# sigsub.net
KiCad netlist of a schematic drawn in Altium Designer
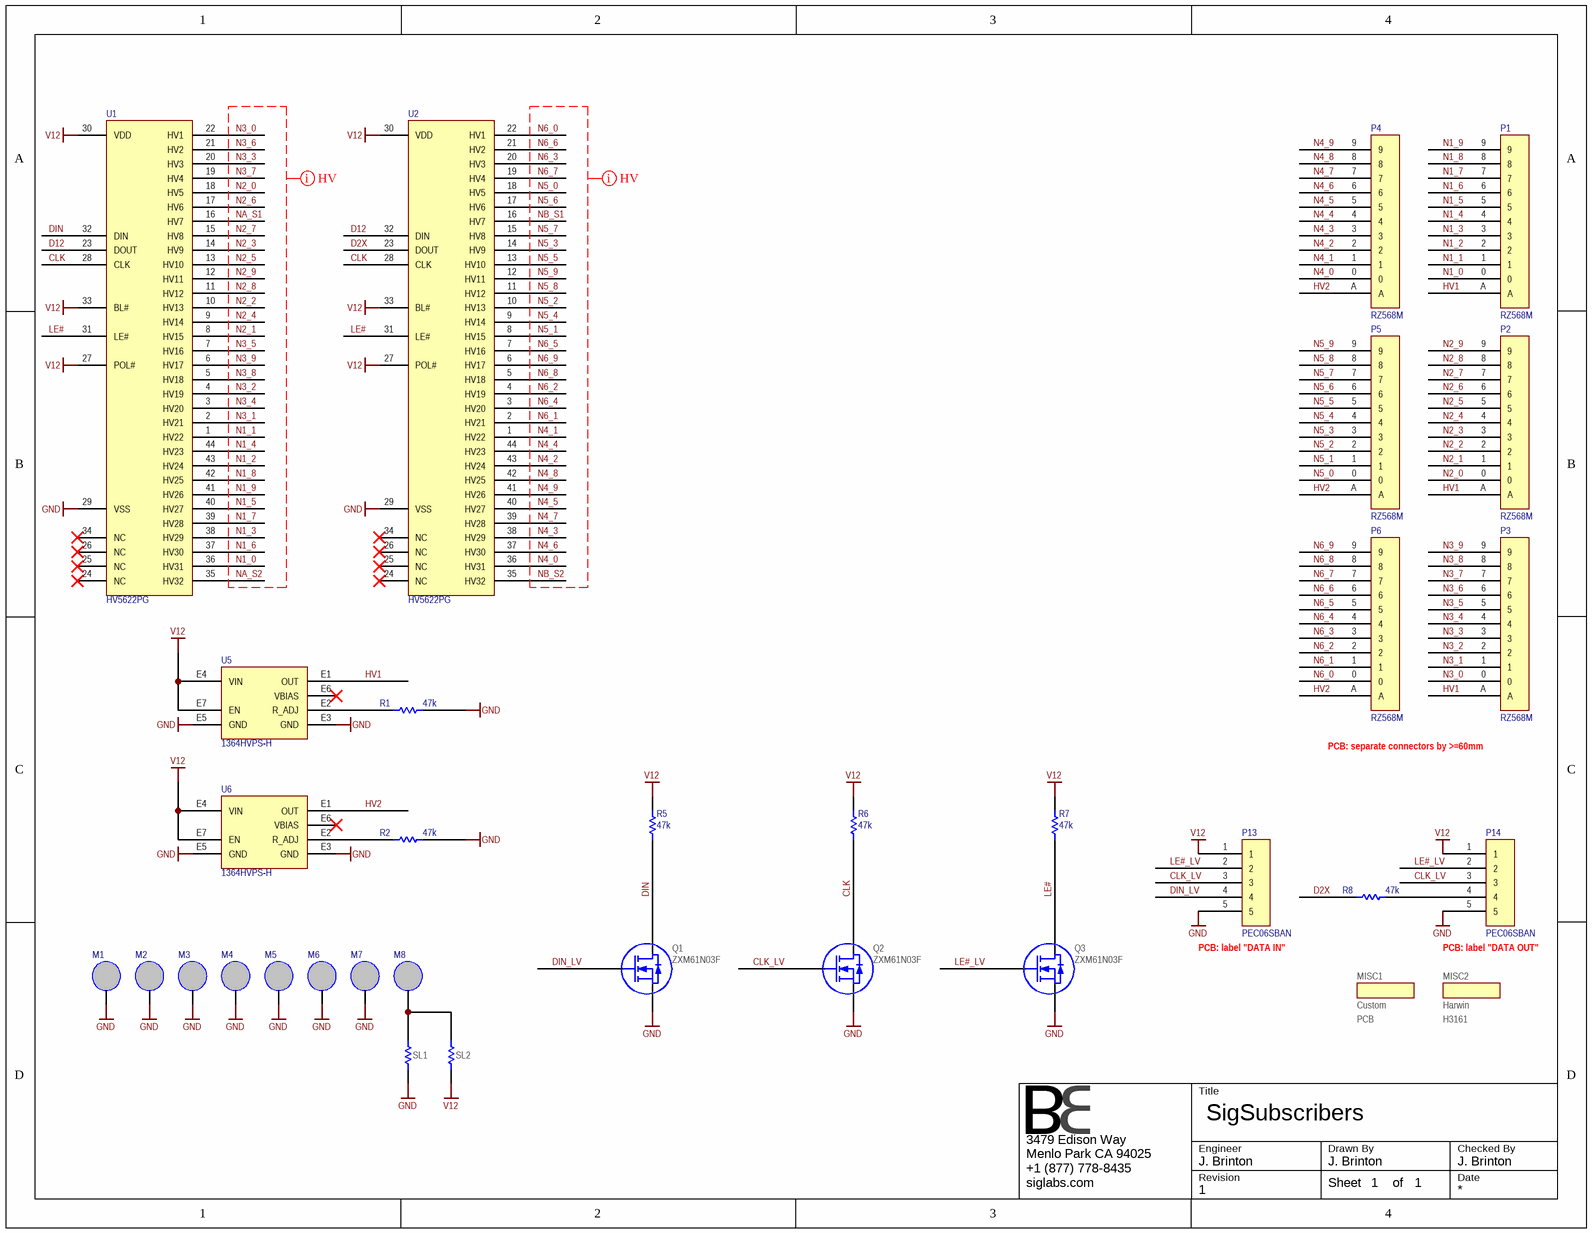
[diagram p0: sigsub.SchDoc]

(export (version "E")
  (design (tool "Eeschema 10.0.6"))
  (components
    (comp (ref "M1") (value "MOUNT") (footprint "MOUNT1-4_20") (libsource (lib "generic") (part "MOUNT")))
    (comp (ref "M2") (value "MOUNT") (footprint "MOUNT1-4_20") (libsource (lib "generic") (part "MOUNT")))
    (comp (ref "M3") (value "MOUNT") (footprint "MOUNT1-4_20") (libsource (lib "generic") (part "MOUNT")))
    (comp (ref "M4") (value "MOUNT") (footprint "MOUNT1-4_20") (libsource (lib "generic") (part "MOUNT")))
    (comp (ref "M5") (value "MOUNT") (footprint "MOUNT1-4_20") (libsource (lib "generic") (part "MOUNT")))
    (comp (ref "M6") (value "MOUNT") (footprint "MOUNT1-4_20") (libsource (lib "generic") (part "MOUNT")))
    (comp (ref "M7") (value "MOUNT") (footprint "MOUNT1-4_20") (libsource (lib "generic") (part "MOUNT")))
    (comp (ref "M8") (value "MOUNT") (footprint "MOUNT1-4_20") (libsource (lib "generic") (part "MOUNT")))
    (comp (ref "MISC1")
      (value "PCB")
      (fields (field (name "MANUFACTURER") "Custom"))
      (libsource (lib "harwin") (part "M50-1900005"))
    )
    (comp (ref "MISC2")
      (value "H3161")
      (description "Pin Receptacle")
      (fields (field (name "MANUFACTURER") "Harwin"))
      (libsource (lib "harwin") (part "M50-1900005"))
    )
    (comp (ref "P1")
      (value "RZ568M")
      (footprint "RZ568M")
      (description "Nixie Tube Socket")
      (fields (field (name "MANUFACTURER") "Glow Tube Research"))
      (libsource (lib "sigsub") (part "RZ568M"))
    )
    (comp (ref "P2")
      (value "RZ568M")
      (footprint "RZ568M")
      (description "Nixie Tube Socket")
      (fields (field (name "MANUFACTURER") "Glow Tube Research"))
      (libsource (lib "sigsub") (part "RZ568M"))
    )
    (comp (ref "P3")
      (value "RZ568M")
      (footprint "RZ568M")
      (description "Nixie Tube Socket")
      (fields (field (name "MANUFACTURER") "Glow Tube Research"))
      (libsource (lib "sigsub") (part "RZ568M"))
    )
    (comp (ref "P4")
      (value "RZ568M")
      (footprint "RZ568M")
      (description "Nixie Tube Socket")
      (fields (field (name "MANUFACTURER") "Glow Tube Research"))
      (libsource (lib "sigsub") (part "RZ568M"))
    )
    (comp (ref "P5")
      (value "RZ568M")
      (footprint "RZ568M")
      (description "Nixie Tube Socket")
      (fields (field (name "MANUFACTURER") "Glow Tube Research"))
      (libsource (lib "sigsub") (part "RZ568M"))
    )
    (comp (ref "P6")
      (value "RZ568M")
      (footprint "RZ568M")
      (description "Nixie Tube Socket")
      (fields (field (name "MANUFACTURER") "Glow Tube Research"))
      (libsource (lib "sigsub") (part "RZ568M"))
    )
    (comp (ref "P13")
      (value "PEC06SBAN")
      (footprint "HDR1X5")
      (description "Header, 5-Pin, Right Angle, 0.1\" pitch")
      (fields (field (name "MANUFACTURER") "Sullins"))
      (libsource (lib "sigsub") (part "PEC06SBAN"))
    )
    (comp (ref "P14")
      (value "PEC06SBAN")
      (footprint "HDR1X5")
      (description "Header, 5-Pin, Right Angle, 0.1\" pitch")
      (fields (field (name "MANUFACTURER") "Sullins"))
      (libsource (lib "sigsub") (part "PEC06SBAN"))
    )
    (comp (ref "Q1")
      (value "ZXM61N03F")
      (footprint "SOT23")
      (description "N-Channel Enhancement Mode MOSFET transistor")
      (fields (field (name "MANUFACTURER") "Zetex"))
      (libsource (lib "nxp") (part "BSH103"))
    )
    (comp (ref "Q2")
      (value "ZXM61N03F")
      (footprint "SOT23")
      (description "N-Channel Enhancement Mode MOSFET transistor")
      (fields (field (name "MANUFACTURER") "Zetex"))
      (libsource (lib "nxp") (part "BSH103"))
    )
    (comp (ref "Q3")
      (value "ZXM61N03F")
      (footprint "SOT23")
      (description "N-Channel Enhancement Mode MOSFET transistor")
      (fields (field (name "MANUFACTURER") "Zetex"))
      (libsource (lib "nxp") (part "BSH103"))
    )
    (comp (ref "R1")
      (value "47k")
      (footprint "0805")
      (description "Thick Film Resistor 47k +/-1% 0805")
      (fields (field (name "MANUFACTURER") "Panasonic") (field (name "Comment") "ERJ-6ENF4702V"))
      (libsource (lib "generic") (part "RES"))
    )
    (comp (ref "R2")
      (value "47k")
      (footprint "0805")
      (description "Thick Film Resistor 47k +/-1% 0805")
      (fields (field (name "MANUFACTURER") "Panasonic") (field (name "Comment") "ERJ-6ENF4702V"))
      (libsource (lib "generic") (part "RES"))
    )
    (comp (ref "R5")
      (value "47k")
      (footprint "0805")
      (description "Thick Film Resistor 47k +/-1% 0805")
      (fields (field (name "MANUFACTURER") "Panasonic") (field (name "Comment") "ERJ-6ENF4702V"))
      (libsource (lib "generic") (part "RES"))
    )
    (comp (ref "R6")
      (value "47k")
      (footprint "0805")
      (description "Thick Film Resistor 47k +/-1% 0805")
      (fields (field (name "MANUFACTURER") "Panasonic") (field (name "Comment") "ERJ-6ENF4702V"))
      (libsource (lib "generic") (part "RES"))
    )
    (comp (ref "R7")
      (value "47k")
      (footprint "0805")
      (description "Thick Film Resistor 47k +/-1% 0805")
      (fields (field (name "MANUFACTURER") "Panasonic") (field (name "Comment") "ERJ-6ENF4702V"))
      (libsource (lib "generic") (part "RES"))
    )
    (comp (ref "R8")
      (value "47k")
      (footprint "0805")
      (description "Thick Film Resistor 47k +/-1% 0805")
      (fields (field (name "MANUFACTURER") "Panasonic") (field (name "Comment") "ERJ-6ENF4702V"))
      (libsource (lib "generic") (part "RES"))
    )
    (comp (ref "SL1")
      (value "SOLDER_LINK")
      (footprint "SOLDERLINK0603X26N")
      (description "Solder Link")
      (libsource (lib "generic") (part "RES"))
    )
    (comp (ref "SL2")
      (value "SOLDER_LINK")
      (footprint "SOLDERLINK0603X26N")
      (description "Solder Link")
      (libsource (lib "generic") (part "RES"))
    )
    (comp (ref "U1")
      (value "HV5622PG")
      (footprint "QFP44P80_1390X1390X235L88X37N")
      (description "32-Channel Serial to Parallel Converter")
      (fields (field (name "MANUFACTURER") "Microchip"))
      (libsource (lib "sigsub") (part "HV5622PG"))
    )
    (comp (ref "U2")
      (value "HV5622PG")
      (footprint "QFP44P80_1390X1390X235L88X37N")
      (description "32-Channel Serial to Parallel Converter")
      (fields (field (name "MANUFACTURER") "Microchip"))
      (libsource (lib "sigsub") (part "HV5622PG"))
    )
    (comp (ref "U5")
      (value "1364HVPS-H")
      (footprint "1364HVPS-H")
      (description "High Voltage Power Supply")
      (fields (field (name "MANUFACTURER") "Taylor Electronics"))
      (libsource (lib "sigsub") (part "1364HVPS-H"))
    )
    (comp (ref "U6")
      (value "1364HVPS-H")
      (footprint "1364HVPS-H")
      (description "High Voltage Power Supply")
      (fields (field (name "MANUFACTURER") "Taylor Electronics"))
      (libsource (lib "sigsub") (part "1364HVPS-H"))
    )
  )
  (nets
    (net (code "1") (name "/CLK") (class "Default")
      (node (ref "Q2") (pin "3") (pinfunction "D_3") (pintype "passive"))
      (node (ref "R6") (pin "1") (pinfunction "1_1") (pintype "passive"))
      (node (ref "U1") (pin "28") (pinfunction "CLK_28") (pintype "passive"))
      (node (ref "U2") (pin "28") (pinfunction "CLK_28") (pintype "passive"))
    )
    (net (code "2") (name "/CLK_LV") (class "Default")
      (node (ref "P13") (pin "3") (pinfunction "3_3") (pintype "passive"))
      (node (ref "P14") (pin "3") (pinfunction "3_3") (pintype "passive"))
      (node (ref "Q2") (pin "1") (pinfunction "G_1") (pintype "passive"))
    )
    (net (code "3") (name "/D2X") (class "Default")
      (node (ref "R8") (pin "1") (pinfunction "1_1") (pintype "passive"))
      (node (ref "U2") (pin "23") (pinfunction "DOUT_23") (pintype "passive"))
    )
    (net (code "4") (name "/D12") (class "Default")
      (node (ref "U1") (pin "23") (pinfunction "DOUT_23") (pintype "passive"))
      (node (ref "U2") (pin "32") (pinfunction "DIN_32") (pintype "passive"))
    )
    (net (code "5") (name "/DIN") (class "Default")
      (node (ref "Q1") (pin "3") (pinfunction "D_3") (pintype "passive"))
      (node (ref "R5") (pin "1") (pinfunction "1_1") (pintype "passive"))
      (node (ref "U1") (pin "32") (pinfunction "DIN_32") (pintype "passive"))
    )
    (net (code "6") (name "/DIN_LV") (class "Default")
      (node (ref "P13") (pin "4") (pinfunction "4_4") (pintype "passive"))
      (node (ref "Q1") (pin "1") (pinfunction "G_1") (pintype "passive"))
    )
    (net (code "7") (name "/HV1") (class "Default")
      (node (ref "P1") (pin "A") (pinfunction "A_A") (pintype "passive"))
      (node (ref "P2") (pin "A") (pinfunction "A_A") (pintype "passive"))
      (node (ref "P3") (pin "A") (pinfunction "A_A") (pintype "passive"))
      (node (ref "U5") (pin "E1") (pinfunction "OUT_E1") (pintype "passive"))
    )
    (net (code "8") (name "/HV2") (class "Default")
      (node (ref "P4") (pin "A") (pinfunction "A_A") (pintype "passive"))
      (node (ref "P5") (pin "A") (pinfunction "A_A") (pintype "passive"))
      (node (ref "P6") (pin "A") (pinfunction "A_A") (pintype "passive"))
      (node (ref "U6") (pin "E1") (pinfunction "OUT_E1") (pintype "passive"))
    )
    (net (code "9") (name "/LE#") (class "Default")
      (node (ref "Q3") (pin "3") (pinfunction "D_3") (pintype "passive"))
      (node (ref "R7") (pin "1") (pinfunction "1_1") (pintype "passive"))
      (node (ref "U1") (pin "31") (pinfunction "LE#_31") (pintype "passive"))
      (node (ref "U2") (pin "31") (pinfunction "LE#_31") (pintype "passive"))
    )
    (net (code "10") (name "/LE#_LV") (class "Default")
      (node (ref "P13") (pin "2") (pinfunction "2_2") (pintype "passive"))
      (node (ref "P14") (pin "2") (pinfunction "2_2") (pintype "passive"))
      (node (ref "Q3") (pin "1") (pinfunction "G_1") (pintype "passive"))
    )
    (net (code "11") (name "/N1_0") (class "Default")
      (node (ref "P1") (pin "0") (pinfunction "0_0") (pintype "passive"))
      (node (ref "U1") (pin "36") (pinfunction "HV31_36") (pintype "passive"))
    )
    (net (code "12") (name "/N1_1") (class "Default")
      (node (ref "P1") (pin "1") (pinfunction "1_1") (pintype "passive"))
      (node (ref "U1") (pin "1") (pinfunction "HV22_1") (pintype "passive"))
    )
    (net (code "13") (name "/N1_2") (class "Default")
      (node (ref "P1") (pin "2") (pinfunction "2_2") (pintype "passive"))
      (node (ref "U1") (pin "43") (pinfunction "HV24_43") (pintype "passive"))
    )
    (net (code "14") (name "/N1_3") (class "Default")
      (node (ref "P1") (pin "3") (pinfunction "3_3") (pintype "passive"))
      (node (ref "U1") (pin "38") (pinfunction "HV29_38") (pintype "passive"))
    )
    (net (code "15") (name "/N1_4") (class "Default")
      (node (ref "P1") (pin "4") (pinfunction "4_4") (pintype "passive"))
      (node (ref "U1") (pin "44") (pinfunction "HV23_44") (pintype "passive"))
    )
    (net (code "16") (name "/N1_5") (class "Default")
      (node (ref "P1") (pin "5") (pinfunction "5_5") (pintype "passive"))
      (node (ref "U1") (pin "40") (pinfunction "HV27_40") (pintype "passive"))
    )
    (net (code "17") (name "/N1_6") (class "Default")
      (node (ref "P1") (pin "6") (pinfunction "6_6") (pintype "passive"))
      (node (ref "U1") (pin "37") (pinfunction "HV30_37") (pintype "passive"))
    )
    (net (code "18") (name "/N1_7") (class "Default")
      (node (ref "P1") (pin "7") (pinfunction "7_7") (pintype "passive"))
      (node (ref "U1") (pin "39") (pinfunction "HV28_39") (pintype "passive"))
    )
    (net (code "19") (name "/N1_8") (class "Default")
      (node (ref "P1") (pin "8") (pinfunction "8_8") (pintype "passive"))
      (node (ref "U1") (pin "42") (pinfunction "HV25_42") (pintype "passive"))
    )
    (net (code "20") (name "/N1_9") (class "Default")
      (node (ref "P1") (pin "9") (pinfunction "9_9") (pintype "passive"))
      (node (ref "U1") (pin "41") (pinfunction "HV26_41") (pintype "passive"))
    )
    (net (code "21") (name "/N2_0") (class "Default")
      (node (ref "P2") (pin "0") (pinfunction "0_0") (pintype "passive"))
      (node (ref "U1") (pin "18") (pinfunction "HV5_18") (pintype "passive"))
    )
    (net (code "22") (name "/N2_1") (class "Default")
      (node (ref "P2") (pin "1") (pinfunction "1_1") (pintype "passive"))
      (node (ref "U1") (pin "8") (pinfunction "HV15_8") (pintype "passive"))
    )
    (net (code "23") (name "/N2_2") (class "Default")
      (node (ref "P2") (pin "2") (pinfunction "2_2") (pintype "passive"))
      (node (ref "U1") (pin "10") (pinfunction "HV13_10") (pintype "passive"))
    )
    (net (code "24") (name "/N2_3") (class "Default")
      (node (ref "P2") (pin "3") (pinfunction "3_3") (pintype "passive"))
      (node (ref "U1") (pin "14") (pinfunction "HV9_14") (pintype "passive"))
    )
    (net (code "25") (name "/N2_4") (class "Default")
      (node (ref "P2") (pin "4") (pinfunction "4_4") (pintype "passive"))
      (node (ref "U1") (pin "9") (pinfunction "HV14_9") (pintype "passive"))
    )
    (net (code "26") (name "/N2_5") (class "Default")
      (node (ref "P2") (pin "5") (pinfunction "5_5") (pintype "passive"))
      (node (ref "U1") (pin "13") (pinfunction "HV10_13") (pintype "passive"))
    )
    (net (code "27") (name "/N2_6") (class "Default")
      (node (ref "P2") (pin "6") (pinfunction "6_6") (pintype "passive"))
      (node (ref "U1") (pin "17") (pinfunction "HV6_17") (pintype "passive"))
    )
    (net (code "28") (name "/N2_7") (class "Default")
      (node (ref "P2") (pin "7") (pinfunction "7_7") (pintype "passive"))
      (node (ref "U1") (pin "15") (pinfunction "HV8_15") (pintype "passive"))
    )
    (net (code "29") (name "/N2_8") (class "Default")
      (node (ref "P2") (pin "8") (pinfunction "8_8") (pintype "passive"))
      (node (ref "U1") (pin "11") (pinfunction "HV12_11") (pintype "passive"))
    )
    (net (code "30") (name "/N2_9") (class "Default")
      (node (ref "P2") (pin "9") (pinfunction "9_9") (pintype "passive"))
      (node (ref "U1") (pin "12") (pinfunction "HV11_12") (pintype "passive"))
    )
    (net (code "31") (name "/N3_0") (class "Default")
      (node (ref "P3") (pin "0") (pinfunction "0_0") (pintype "passive"))
      (node (ref "U1") (pin "22") (pinfunction "HV1_22") (pintype "passive"))
    )
    (net (code "32") (name "/N3_1") (class "Default")
      (node (ref "P3") (pin "1") (pinfunction "1_1") (pintype "passive"))
      (node (ref "U1") (pin "2") (pinfunction "HV21_2") (pintype "passive"))
    )
    (net (code "33") (name "/N3_2") (class "Default")
      (node (ref "P3") (pin "2") (pinfunction "2_2") (pintype "passive"))
      (node (ref "U1") (pin "4") (pinfunction "HV19_4") (pintype "passive"))
    )
    (net (code "34") (name "/N3_3") (class "Default")
      (node (ref "P3") (pin "3") (pinfunction "3_3") (pintype "passive"))
      (node (ref "U1") (pin "20") (pinfunction "HV3_20") (pintype "passive"))
    )
    (net (code "35") (name "/N3_4") (class "Default")
      (node (ref "P3") (pin "4") (pinfunction "4_4") (pintype "passive"))
      (node (ref "U1") (pin "3") (pinfunction "HV20_3") (pintype "passive"))
    )
    (net (code "36") (name "/N3_5") (class "Default")
      (node (ref "P3") (pin "5") (pinfunction "5_5") (pintype "passive"))
      (node (ref "U1") (pin "7") (pinfunction "HV16_7") (pintype "passive"))
    )
    (net (code "37") (name "/N3_6") (class "Default")
      (node (ref "P3") (pin "6") (pinfunction "6_6") (pintype "passive"))
      (node (ref "U1") (pin "21") (pinfunction "HV2_21") (pintype "passive"))
    )
    (net (code "38") (name "/N3_7") (class "Default")
      (node (ref "P3") (pin "7") (pinfunction "7_7") (pintype "passive"))
      (node (ref "U1") (pin "19") (pinfunction "HV4_19") (pintype "passive"))
    )
    (net (code "39") (name "/N3_8") (class "Default")
      (node (ref "P3") (pin "8") (pinfunction "8_8") (pintype "passive"))
      (node (ref "U1") (pin "5") (pinfunction "HV18_5") (pintype "passive"))
    )
    (net (code "40") (name "/N3_9") (class "Default")
      (node (ref "P3") (pin "9") (pinfunction "9_9") (pintype "passive"))
      (node (ref "U1") (pin "6") (pinfunction "HV17_6") (pintype "passive"))
    )
    (net (code "41") (name "/N4_0") (class "Default")
      (node (ref "P4") (pin "0") (pinfunction "0_0") (pintype "passive"))
      (node (ref "U2") (pin "36") (pinfunction "HV31_36") (pintype "passive"))
    )
    (net (code "42") (name "/N4_1") (class "Default")
      (node (ref "P4") (pin "1") (pinfunction "1_1") (pintype "passive"))
      (node (ref "U2") (pin "1") (pinfunction "HV22_1") (pintype "passive"))
    )
    (net (code "43") (name "/N4_2") (class "Default")
      (node (ref "P4") (pin "2") (pinfunction "2_2") (pintype "passive"))
      (node (ref "U2") (pin "43") (pinfunction "HV24_43") (pintype "passive"))
    )
    (net (code "44") (name "/N4_3") (class "Default")
      (node (ref "P4") (pin "3") (pinfunction "3_3") (pintype "passive"))
      (node (ref "U2") (pin "38") (pinfunction "HV29_38") (pintype "passive"))
    )
    (net (code "45") (name "/N4_4") (class "Default")
      (node (ref "P4") (pin "4") (pinfunction "4_4") (pintype "passive"))
      (node (ref "U2") (pin "44") (pinfunction "HV23_44") (pintype "passive"))
    )
    (net (code "46") (name "/N4_5") (class "Default")
      (node (ref "P4") (pin "5") (pinfunction "5_5") (pintype "passive"))
      (node (ref "U2") (pin "40") (pinfunction "HV27_40") (pintype "passive"))
    )
    (net (code "47") (name "/N4_6") (class "Default")
      (node (ref "P4") (pin "6") (pinfunction "6_6") (pintype "passive"))
      (node (ref "U2") (pin "37") (pinfunction "HV30_37") (pintype "passive"))
    )
    (net (code "48") (name "/N4_7") (class "Default")
      (node (ref "P4") (pin "7") (pinfunction "7_7") (pintype "passive"))
      (node (ref "U2") (pin "39") (pinfunction "HV28_39") (pintype "passive"))
    )
    (net (code "49") (name "/N4_8") (class "Default")
      (node (ref "P4") (pin "8") (pinfunction "8_8") (pintype "passive"))
      (node (ref "U2") (pin "42") (pinfunction "HV25_42") (pintype "passive"))
    )
    (net (code "50") (name "/N4_9") (class "Default")
      (node (ref "P4") (pin "9") (pinfunction "9_9") (pintype "passive"))
      (node (ref "U2") (pin "41") (pinfunction "HV26_41") (pintype "passive"))
    )
    (net (code "51") (name "/N5_0") (class "Default")
      (node (ref "P5") (pin "0") (pinfunction "0_0") (pintype "passive"))
      (node (ref "U2") (pin "18") (pinfunction "HV5_18") (pintype "passive"))
    )
    (net (code "52") (name "/N5_1") (class "Default")
      (node (ref "P5") (pin "1") (pinfunction "1_1") (pintype "passive"))
      (node (ref "U2") (pin "8") (pinfunction "HV15_8") (pintype "passive"))
    )
    (net (code "53") (name "/N5_2") (class "Default")
      (node (ref "P5") (pin "2") (pinfunction "2_2") (pintype "passive"))
      (node (ref "U2") (pin "10") (pinfunction "HV13_10") (pintype "passive"))
    )
    (net (code "54") (name "/N5_3") (class "Default")
      (node (ref "P5") (pin "3") (pinfunction "3_3") (pintype "passive"))
      (node (ref "U2") (pin "14") (pinfunction "HV9_14") (pintype "passive"))
    )
    (net (code "55") (name "/N5_4") (class "Default")
      (node (ref "P5") (pin "4") (pinfunction "4_4") (pintype "passive"))
      (node (ref "U2") (pin "9") (pinfunction "HV14_9") (pintype "passive"))
    )
    (net (code "56") (name "/N5_5") (class "Default")
      (node (ref "P5") (pin "5") (pinfunction "5_5") (pintype "passive"))
      (node (ref "U2") (pin "13") (pinfunction "HV10_13") (pintype "passive"))
    )
    (net (code "57") (name "/N5_6") (class "Default")
      (node (ref "P5") (pin "6") (pinfunction "6_6") (pintype "passive"))
      (node (ref "U2") (pin "17") (pinfunction "HV6_17") (pintype "passive"))
    )
    (net (code "58") (name "/N5_7") (class "Default")
      (node (ref "P5") (pin "7") (pinfunction "7_7") (pintype "passive"))
      (node (ref "U2") (pin "15") (pinfunction "HV8_15") (pintype "passive"))
    )
    (net (code "59") (name "/N5_8") (class "Default")
      (node (ref "P5") (pin "8") (pinfunction "8_8") (pintype "passive"))
      (node (ref "U2") (pin "11") (pinfunction "HV12_11") (pintype "passive"))
    )
    (net (code "60") (name "/N5_9") (class "Default")
      (node (ref "P5") (pin "9") (pinfunction "9_9") (pintype "passive"))
      (node (ref "U2") (pin "12") (pinfunction "HV11_12") (pintype "passive"))
    )
    (net (code "61") (name "/N6_0") (class "Default")
      (node (ref "P6") (pin "0") (pinfunction "0_0") (pintype "passive"))
      (node (ref "U2") (pin "22") (pinfunction "HV1_22") (pintype "passive"))
    )
    (net (code "62") (name "/N6_1") (class "Default")
      (node (ref "P6") (pin "1") (pinfunction "1_1") (pintype "passive"))
      (node (ref "U2") (pin "2") (pinfunction "HV21_2") (pintype "passive"))
    )
    (net (code "63") (name "/N6_2") (class "Default")
      (node (ref "P6") (pin "2") (pinfunction "2_2") (pintype "passive"))
      (node (ref "U2") (pin "4") (pinfunction "HV19_4") (pintype "passive"))
    )
    (net (code "64") (name "/N6_3") (class "Default")
      (node (ref "P6") (pin "3") (pinfunction "3_3") (pintype "passive"))
      (node (ref "U2") (pin "20") (pinfunction "HV3_20") (pintype "passive"))
    )
    (net (code "65") (name "/N6_4") (class "Default")
      (node (ref "P6") (pin "4") (pinfunction "4_4") (pintype "passive"))
      (node (ref "U2") (pin "3") (pinfunction "HV20_3") (pintype "passive"))
    )
    (net (code "66") (name "/N6_5") (class "Default")
      (node (ref "P6") (pin "5") (pinfunction "5_5") (pintype "passive"))
      (node (ref "U2") (pin "7") (pinfunction "HV16_7") (pintype "passive"))
    )
    (net (code "67") (name "/N6_6") (class "Default")
      (node (ref "P6") (pin "6") (pinfunction "6_6") (pintype "passive"))
      (node (ref "U2") (pin "21") (pinfunction "HV2_21") (pintype "passive"))
    )
    (net (code "68") (name "/N6_7") (class "Default")
      (node (ref "P6") (pin "7") (pinfunction "7_7") (pintype "passive"))
      (node (ref "U2") (pin "19") (pinfunction "HV4_19") (pintype "passive"))
    )
    (net (code "69") (name "/N6_8") (class "Default")
      (node (ref "P6") (pin "8") (pinfunction "8_8") (pintype "passive"))
      (node (ref "U2") (pin "5") (pinfunction "HV18_5") (pintype "passive"))
    )
    (net (code "70") (name "/N6_9") (class "Default")
      (node (ref "P6") (pin "9") (pinfunction "9_9") (pintype "passive"))
      (node (ref "U2") (pin "6") (pinfunction "HV17_6") (pintype "passive"))
    )
    (net (code "71") (name "/NA_S1") (class "Default")
      (node (ref "U1") (pin "16") (pinfunction "HV7_16") (pintype "passive"))
    )
    (net (code "72") (name "/NA_S2") (class "Default")
      (node (ref "U1") (pin "35") (pinfunction "HV32_35") (pintype "passive"))
    )
    (net (code "73") (name "/NB_S1") (class "Default")
      (node (ref "U2") (pin "16") (pinfunction "HV7_16") (pintype "passive"))
    )
    (net (code "74") (name "/NB_S2") (class "Default")
      (node (ref "U2") (pin "35") (pinfunction "HV32_35") (pintype "passive"))
    )
    (net (code "75") (name "GND") (class "Default")
      (node (ref "M1") (pin "1") (pinfunction "MNT_1") (pintype "passive"))
      (node (ref "M2") (pin "1") (pinfunction "MNT_1") (pintype "passive"))
      (node (ref "M3") (pin "1") (pinfunction "MNT_1") (pintype "passive"))
      (node (ref "M4") (pin "1") (pinfunction "MNT_1") (pintype "passive"))
      (node (ref "M5") (pin "1") (pinfunction "MNT_1") (pintype "passive"))
      (node (ref "M6") (pin "1") (pinfunction "MNT_1") (pintype "passive"))
      (node (ref "M7") (pin "1") (pinfunction "MNT_1") (pintype "passive"))
      (node (ref "P13") (pin "5") (pinfunction "5_5") (pintype "passive"))
      (node (ref "P14") (pin "5") (pinfunction "5_5") (pintype "passive"))
      (node (ref "Q1") (pin "2") (pinfunction "S_2") (pintype "passive"))
      (node (ref "Q2") (pin "2") (pinfunction "S_2") (pintype "passive"))
      (node (ref "Q3") (pin "2") (pinfunction "S_2") (pintype "passive"))
      (node (ref "R1") (pin "2") (pinfunction "2_2") (pintype "passive"))
      (node (ref "R2") (pin "2") (pinfunction "2_2") (pintype "passive"))
      (node (ref "SL1") (pin "2") (pinfunction "2_2") (pintype "passive"))
      (node (ref "U1") (pin "29") (pinfunction "VSS_29") (pintype "passive"))
      (node (ref "U2") (pin "29") (pinfunction "VSS_29") (pintype "passive"))
      (node (ref "U5") (pin "E3") (pinfunction "GND_E3") (pintype "passive"))
      (node (ref "U5") (pin "E5") (pinfunction "GND_E5") (pintype "passive"))
      (node (ref "U6") (pin "E3") (pinfunction "GND_E3") (pintype "passive"))
      (node (ref "U6") (pin "E5") (pinfunction "GND_E5") (pintype "passive"))
    )
    (net (code "76") (name "Net-(M8-MNT)") (class "Default")
      (node (ref "M8") (pin "1") (pinfunction "MNT_1") (pintype "passive"))
      (node (ref "SL1") (pin "1") (pinfunction "1_1") (pintype "passive"))
      (node (ref "SL2") (pin "1") (pinfunction "1_1") (pintype "passive"))
    )
    (net (code "77") (name "Net-(P14-Pad4)") (class "Default")
      (node (ref "P14") (pin "4") (pinfunction "4_4") (pintype "passive"))
      (node (ref "R8") (pin "2") (pinfunction "2_2") (pintype "passive"))
    )
    (net (code "78") (name "Net-(U5-R_ADJ)") (class "Default")
      (node (ref "R1") (pin "1") (pinfunction "1_1") (pintype "passive"))
      (node (ref "U5") (pin "E2") (pinfunction "R_ADJ_E2") (pintype "passive"))
    )
    (net (code "79") (name "Net-(U6-R_ADJ)") (class "Default")
      (node (ref "R2") (pin "1") (pinfunction "1_1") (pintype "passive"))
      (node (ref "U6") (pin "E2") (pinfunction "R_ADJ_E2") (pintype "passive"))
    )
    (net (code "80") (name "V12") (class "Default")
      (node (ref "P13") (pin "1") (pinfunction "1_1") (pintype "passive"))
      (node (ref "P14") (pin "1") (pinfunction "1_1") (pintype "passive"))
      (node (ref "R5") (pin "2") (pinfunction "2_2") (pintype "passive"))
      (node (ref "R6") (pin "2") (pinfunction "2_2") (pintype "passive"))
      (node (ref "R7") (pin "2") (pinfunction "2_2") (pintype "passive"))
      (node (ref "SL2") (pin "2") (pinfunction "2_2") (pintype "passive"))
      (node (ref "U1") (pin "27") (pinfunction "POL#_27") (pintype "passive"))
      (node (ref "U1") (pin "30") (pinfunction "VDD_30") (pintype "passive"))
      (node (ref "U1") (pin "33") (pinfunction "BL#_33") (pintype "passive"))
      (node (ref "U2") (pin "27") (pinfunction "POL#_27") (pintype "passive"))
      (node (ref "U2") (pin "30") (pinfunction "VDD_30") (pintype "passive"))
      (node (ref "U2") (pin "33") (pinfunction "BL#_33") (pintype "passive"))
      (node (ref "U5") (pin "E4") (pinfunction "VIN_E4") (pintype "passive"))
      (node (ref "U5") (pin "E7") (pinfunction "EN_E7") (pintype "passive"))
      (node (ref "U6") (pin "E4") (pinfunction "VIN_E4") (pintype "passive"))
      (node (ref "U6") (pin "E7") (pinfunction "EN_E7") (pintype "passive"))
    )
    (net (code "81") (name "unconnected-(U1-NC-Pad24)") (class "Default")
      (node (ref "U1") (pin "24") (pinfunction "NC_24") (pintype "passive+no_connect"))
    )
    (net (code "82") (name "unconnected-(U1-NC-Pad25)") (class "Default")
      (node (ref "U1") (pin "25") (pinfunction "NC_25") (pintype "passive+no_connect"))
    )
    (net (code "83") (name "unconnected-(U1-NC-Pad26)") (class "Default")
      (node (ref "U1") (pin "26") (pinfunction "NC_26") (pintype "passive+no_connect"))
    )
    (net (code "84") (name "unconnected-(U1-NC-Pad34)") (class "Default")
      (node (ref "U1") (pin "34") (pinfunction "NC_34") (pintype "passive+no_connect"))
    )
    (net (code "85") (name "unconnected-(U2-NC-Pad24)") (class "Default")
      (node (ref "U2") (pin "24") (pinfunction "NC_24") (pintype "passive+no_connect"))
    )
    (net (code "86") (name "unconnected-(U2-NC-Pad25)") (class "Default")
      (node (ref "U2") (pin "25") (pinfunction "NC_25") (pintype "passive+no_connect"))
    )
    (net (code "87") (name "unconnected-(U2-NC-Pad26)") (class "Default")
      (node (ref "U2") (pin "26") (pinfunction "NC_26") (pintype "passive+no_connect"))
    )
    (net (code "88") (name "unconnected-(U2-NC-Pad34)") (class "Default")
      (node (ref "U2") (pin "34") (pinfunction "NC_34") (pintype "passive+no_connect"))
    )
    (net (code "89") (name "unconnected-(U5-VBIAS-PadE6)") (class "Default")
      (node (ref "U5") (pin "E6") (pinfunction "VBIAS_E6") (pintype "passive+no_connect"))
    )
    (net (code "90") (name "unconnected-(U6-VBIAS-PadE6)") (class "Default")
      (node (ref "U6") (pin "E6") (pinfunction "VBIAS_E6") (pintype "passive+no_connect"))
    )
  )
)
